# M2_Breakout.net
KiCad netlist of a schematic drawn in Altium Designer
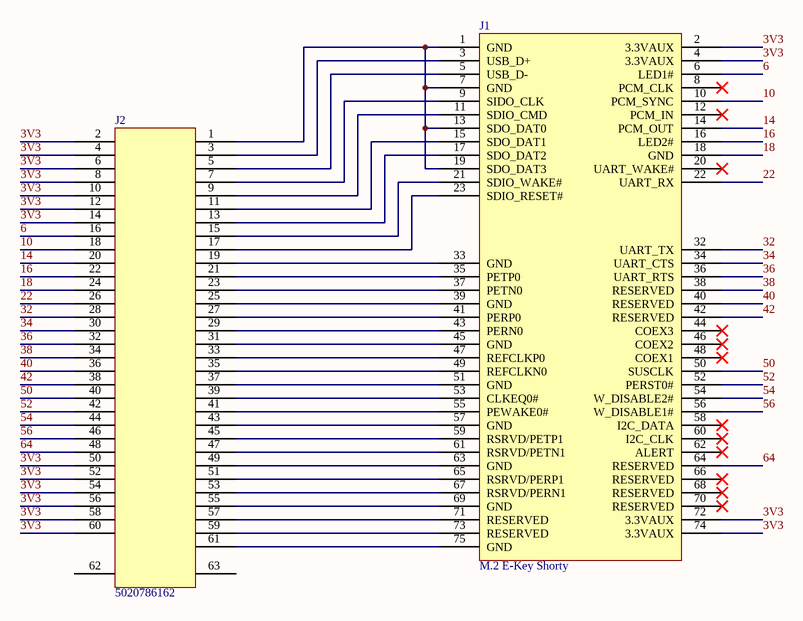
[diagram p0: M2 Breakout.SchDoc]

(export (version "E")
  (design (tool "Eeschema 10.0.6"))
  (components
    (comp (ref "J1")
      (value "M.2 E-Key Shorty")
      (footprint "M.2 E-Key Shorty")
      (libsource (lib "KBuchka-IntLib") (part "M.2 E-Key Shorty"))
    )
    (comp (ref "J2")
      (value "5020786162")
      (footprint "5020786162")
      (description "Conn FPC Connector SKT 61 POS 0.25mm Solder RA SMD T/R")
      (libsource (lib "KBuchka-IntLib") (part "5020786162"))
    )
  )
  (nets
    (net (code "1") (name "/3V3") (class "Default")
      (node (ref "J1") (pin "2") (pinfunction "3.3VAUX_2") (pintype "passive"))
      (node (ref "J1") (pin "4") (pinfunction "3.3VAUX_4") (pintype "passive"))
      (node (ref "J1") (pin "72") (pinfunction "3.3VAUX_72") (pintype "passive"))
      (node (ref "J1") (pin "74") (pinfunction "3.3VAUX_74") (pintype "passive"))
      (node (ref "J2") (pin "10") (pintype "passive"))
      (node (ref "J2") (pin "12") (pintype "passive"))
      (node (ref "J2") (pin "14") (pintype "passive"))
      (node (ref "J2") (pin "2") (pintype "passive"))
      (node (ref "J2") (pin "4") (pintype "passive"))
      (node (ref "J2") (pin "50") (pintype "passive"))
      (node (ref "J2") (pin "52") (pintype "passive"))
      (node (ref "J2") (pin "54") (pintype "passive"))
      (node (ref "J2") (pin "56") (pintype "passive"))
      (node (ref "J2") (pin "58") (pintype "passive"))
      (node (ref "J2") (pin "6") (pintype "passive"))
      (node (ref "J2") (pin "60") (pintype "passive"))
      (node (ref "J2") (pin "8") (pintype "passive"))
    )
    (net (code "2") (name "/6") (class "Default")
      (node (ref "J1") (pin "6") (pinfunction "LED1#_6") (pintype "passive"))
      (node (ref "J2") (pin "16") (pintype "passive"))
    )
    (net (code "3") (name "/10") (class "Default")
      (node (ref "J1") (pin "10") (pinfunction "PCM_SYNC_10") (pintype "passive"))
      (node (ref "J2") (pin "18") (pintype "passive"))
    )
    (net (code "4") (name "/14") (class "Default")
      (node (ref "J1") (pin "14") (pinfunction "PCM_OUT_14") (pintype "passive"))
      (node (ref "J2") (pin "20") (pintype "passive"))
    )
    (net (code "5") (name "/16") (class "Default")
      (node (ref "J1") (pin "16") (pinfunction "LED2#_16") (pintype "passive"))
      (node (ref "J2") (pin "22") (pintype "passive"))
    )
    (net (code "6") (name "/18") (class "Default")
      (node (ref "J1") (pin "18") (pinfunction "GND_18") (pintype "passive"))
      (node (ref "J2") (pin "24") (pintype "passive"))
    )
    (net (code "7") (name "/22") (class "Default")
      (node (ref "J1") (pin "22") (pinfunction "UART_RX_22") (pintype "passive"))
      (node (ref "J2") (pin "26") (pintype "passive"))
    )
    (net (code "8") (name "/32") (class "Default")
      (node (ref "J1") (pin "32") (pinfunction "UART_TX_32") (pintype "passive"))
      (node (ref "J2") (pin "28") (pintype "passive"))
    )
    (net (code "9") (name "/34") (class "Default")
      (node (ref "J1") (pin "34") (pinfunction "UART_CTS_34") (pintype "passive"))
      (node (ref "J2") (pin "30") (pintype "passive"))
    )
    (net (code "10") (name "/36") (class "Default")
      (node (ref "J1") (pin "36") (pinfunction "UART_RTS_36") (pintype "passive"))
      (node (ref "J2") (pin "32") (pintype "passive"))
    )
    (net (code "11") (name "/38") (class "Default")
      (node (ref "J1") (pin "38") (pinfunction "RESERVED_38") (pintype "passive"))
      (node (ref "J2") (pin "34") (pintype "passive"))
    )
    (net (code "12") (name "/40") (class "Default")
      (node (ref "J1") (pin "40") (pinfunction "RESERVED_40") (pintype "passive"))
      (node (ref "J2") (pin "36") (pintype "passive"))
    )
    (net (code "13") (name "/42") (class "Default")
      (node (ref "J1") (pin "42") (pinfunction "RESERVED_42") (pintype "passive"))
      (node (ref "J2") (pin "38") (pintype "passive"))
    )
    (net (code "14") (name "/50") (class "Default")
      (node (ref "J1") (pin "50") (pinfunction "SUSCLK_50") (pintype "passive"))
      (node (ref "J2") (pin "40") (pintype "passive"))
    )
    (net (code "15") (name "/52") (class "Default")
      (node (ref "J1") (pin "52") (pinfunction "PERST0#_52") (pintype "passive"))
      (node (ref "J2") (pin "42") (pintype "passive"))
    )
    (net (code "16") (name "/54") (class "Default")
      (node (ref "J1") (pin "54") (pinfunction "W_DISABLE2#_54") (pintype "passive"))
      (node (ref "J2") (pin "44") (pintype "passive"))
    )
    (net (code "17") (name "/56") (class "Default")
      (node (ref "J1") (pin "56") (pinfunction "W_DISABLE1#_56") (pintype "passive"))
      (node (ref "J2") (pin "46") (pintype "passive"))
    )
    (net (code "18") (name "/64") (class "Default")
      (node (ref "J1") (pin "64") (pinfunction "RESERVED_64") (pintype "passive"))
      (node (ref "J2") (pin "48") (pintype "passive"))
    )
    (net (code "19") (name "Net-(J1-CLKEQ0#)") (class "Default")
      (node (ref "J1") (pin "53") (pinfunction "CLKEQ0#_53") (pintype "passive"))
      (node (ref "J2") (pin "39") (pintype "passive"))
    )
    (net (code "20") (name "Net-(J1-GND-Pad33)") (class "Default")
      (node (ref "J1") (pin "33") (pinfunction "GND_33") (pintype "passive"))
      (node (ref "J2") (pin "19") (pintype "passive"))
    )
    (net (code "21") (name "Net-(J1-GND-Pad39)") (class "Default")
      (node (ref "J1") (pin "39") (pinfunction "GND_39") (pintype "passive"))
      (node (ref "J2") (pin "25") (pintype "passive"))
    )
    (net (code "22") (name "Net-(J1-GND-Pad45)") (class "Default")
      (node (ref "J1") (pin "45") (pinfunction "GND_45") (pintype "passive"))
      (node (ref "J2") (pin "31") (pintype "passive"))
    )
    (net (code "23") (name "Net-(J1-GND-Pad51)") (class "Default")
      (node (ref "J1") (pin "51") (pinfunction "GND_51") (pintype "passive"))
      (node (ref "J2") (pin "37") (pintype "passive"))
    )
    (net (code "24") (name "Net-(J1-GND-Pad57)") (class "Default")
      (node (ref "J1") (pin "57") (pinfunction "GND_57") (pintype "passive"))
      (node (ref "J2") (pin "43") (pintype "passive"))
    )
    (net (code "25") (name "Net-(J1-GND-Pad63)") (class "Default")
      (node (ref "J1") (pin "63") (pinfunction "GND_63") (pintype "passive"))
      (node (ref "J2") (pin "49") (pintype "passive"))
    )
    (net (code "26") (name "Net-(J1-GND-Pad69)") (class "Default")
      (node (ref "J1") (pin "69") (pinfunction "GND_69") (pintype "passive"))
      (node (ref "J2") (pin "55") (pintype "passive"))
    )
    (net (code "27") (name "Net-(J1-GND-Pad75)") (class "Default")
      (node (ref "J1") (pin "75") (pinfunction "GND_75") (pintype "passive"))
      (node (ref "J2") (pin "61") (pintype "passive"))
    )
    (net (code "28") (name "Net-(J1-PERN0)") (class "Default")
      (node (ref "J1") (pin "43") (pinfunction "PERN0_43") (pintype "passive"))
      (node (ref "J2") (pin "29") (pintype "passive"))
    )
    (net (code "29") (name "Net-(J1-PERP0)") (class "Default")
      (node (ref "J1") (pin "41") (pinfunction "PERP0_41") (pintype "passive"))
      (node (ref "J2") (pin "27") (pintype "passive"))
    )
    (net (code "30") (name "Net-(J1-PETN0)") (class "Default")
      (node (ref "J1") (pin "37") (pinfunction "PETN0_37") (pintype "passive"))
      (node (ref "J2") (pin "23") (pintype "passive"))
    )
    (net (code "31") (name "Net-(J1-PETP0)") (class "Default")
      (node (ref "J1") (pin "35") (pinfunction "PETP0_35") (pintype "passive"))
      (node (ref "J2") (pin "21") (pintype "passive"))
    )
    (net (code "32") (name "Net-(J1-PEWAKE0#)") (class "Default")
      (node (ref "J1") (pin "55") (pinfunction "PEWAKE0#_55") (pintype "passive"))
      (node (ref "J2") (pin "41") (pintype "passive"))
    )
    (net (code "33") (name "Net-(J1-REFCLKN0)") (class "Default")
      (node (ref "J1") (pin "49") (pinfunction "REFCLKN0_49") (pintype "passive"))
      (node (ref "J2") (pin "35") (pintype "passive"))
    )
    (net (code "34") (name "Net-(J1-REFCLKP0)") (class "Default")
      (node (ref "J1") (pin "47") (pinfunction "REFCLKP0_47") (pintype "passive"))
      (node (ref "J2") (pin "33") (pintype "passive"))
    )
    (net (code "35") (name "Net-(J1-RESERVED-Pad71)") (class "Default")
      (node (ref "J1") (pin "71") (pinfunction "RESERVED_71") (pintype "passive"))
      (node (ref "J2") (pin "57") (pintype "passive"))
    )
    (net (code "36") (name "Net-(J1-RESERVED-Pad73)") (class "Default")
      (node (ref "J1") (pin "73") (pinfunction "RESERVED_73") (pintype "passive"))
      (node (ref "J2") (pin "59") (pintype "passive"))
    )
    (net (code "37") (name "Net-(J1-RSRVD{slash}PERN1)") (class "Default")
      (node (ref "J1") (pin "67") (pinfunction "RSRVD/PERN1_67") (pintype "passive"))
      (node (ref "J2") (pin "53") (pintype "passive"))
    )
    (net (code "38") (name "Net-(J1-RSRVD{slash}PERP1)") (class "Default")
      (node (ref "J1") (pin "65") (pinfunction "RSRVD/PERP1_65") (pintype "passive"))
      (node (ref "J2") (pin "51") (pintype "passive"))
    )
    (net (code "39") (name "Net-(J1-RSRVD{slash}PETN1)") (class "Default")
      (node (ref "J1") (pin "61") (pinfunction "RSRVD/PETN1_61") (pintype "passive"))
      (node (ref "J2") (pin "47") (pintype "passive"))
    )
    (net (code "40") (name "Net-(J1-RSRVD{slash}PETP1)") (class "Default")
      (node (ref "J1") (pin "59") (pinfunction "RSRVD/PETP1_59") (pintype "passive"))
      (node (ref "J2") (pin "45") (pintype "passive"))
    )
    (net (code "41") (name "Net-(J1-SDIO_CMD)") (class "Default")
      (node (ref "J1") (pin "11") (pinfunction "SDIO_CMD_11") (pintype "passive"))
      (node (ref "J2") (pin "9") (pintype "passive"))
    )
    (net (code "42") (name "Net-(J1-SDIO_RESET#)") (class "Default")
      (node (ref "J1") (pin "23") (pinfunction "SDIO_RESET#_23") (pintype "passive"))
      (node (ref "J2") (pin "17") (pintype "passive"))
    )
    (net (code "43") (name "Net-(J1-SDIO_WAKE#)") (class "Default")
      (node (ref "J1") (pin "21") (pinfunction "SDIO_WAKE#_21") (pintype "passive"))
      (node (ref "J2") (pin "15") (pintype "passive"))
    )
    (net (code "44") (name "Net-(J1-SDO_DAT0)") (class "Default")
      (node (ref "J1") (pin "1") (pinfunction "GND_1") (pintype "passive"))
      (node (ref "J1") (pin "13") (pinfunction "SDO_DAT0_13") (pintype "passive"))
      (node (ref "J1") (pin "19") (pinfunction "SDO_DAT3_19") (pintype "passive"))
      (node (ref "J1") (pin "7") (pinfunction "GND_7") (pintype "passive"))
      (node (ref "J2") (pin "1") (pintype "passive"))
    )
    (net (code "45") (name "Net-(J1-SDO_DAT1)") (class "Default")
      (node (ref "J1") (pin "15") (pinfunction "SDO_DAT1_15") (pintype "passive"))
      (node (ref "J2") (pin "11") (pintype "passive"))
    )
    (net (code "46") (name "Net-(J1-SDO_DAT2)") (class "Default")
      (node (ref "J1") (pin "17") (pinfunction "SDO_DAT2_17") (pintype "passive"))
      (node (ref "J2") (pin "13") (pintype "passive"))
    )
    (net (code "47") (name "Net-(J1-SIDO_CLK)") (class "Default")
      (node (ref "J1") (pin "9") (pinfunction "SIDO_CLK_9") (pintype "passive"))
      (node (ref "J2") (pin "7") (pintype "passive"))
    )
    (net (code "48") (name "Net-(J1-USB_D+)") (class "Default")
      (node (ref "J1") (pin "3") (pinfunction "USB_D+_3") (pintype "passive"))
      (node (ref "J2") (pin "3") (pintype "passive"))
    )
    (net (code "49") (name "Net-(J1-USB_D-)") (class "Default")
      (node (ref "J1") (pin "5") (pinfunction "USB_D-_5") (pintype "passive"))
      (node (ref "J2") (pin "5") (pintype "passive"))
    )
    (net (code "50") (name "unconnected-(J1-ALERT-Pad62)") (class "Default")
      (node (ref "J1") (pin "62") (pinfunction "ALERT_62") (pintype "passive+no_connect"))
    )
    (net (code "51") (name "unconnected-(J1-COEX1-Pad48)") (class "Default")
      (node (ref "J1") (pin "48") (pinfunction "COEX1_48") (pintype "passive+no_connect"))
    )
    (net (code "52") (name "unconnected-(J1-COEX2-Pad46)") (class "Default")
      (node (ref "J1") (pin "46") (pinfunction "COEX2_46") (pintype "passive+no_connect"))
    )
    (net (code "53") (name "unconnected-(J1-COEX3-Pad44)") (class "Default")
      (node (ref "J1") (pin "44") (pinfunction "COEX3_44") (pintype "passive+no_connect"))
    )
    (net (code "54") (name "unconnected-(J1-I2C_CLK-Pad60)") (class "Default")
      (node (ref "J1") (pin "60") (pinfunction "I2C_CLK_60") (pintype "passive+no_connect"))
    )
    (net (code "55") (name "unconnected-(J1-I2C_DATA-Pad58)") (class "Default")
      (node (ref "J1") (pin "58") (pinfunction "I2C_DATA_58") (pintype "passive+no_connect"))
    )
    (net (code "56") (name "unconnected-(J1-PCM_CLK-Pad8)") (class "Default")
      (node (ref "J1") (pin "8") (pinfunction "PCM_CLK_8") (pintype "passive+no_connect"))
    )
    (net (code "57") (name "unconnected-(J1-PCM_IN-Pad12)") (class "Default")
      (node (ref "J1") (pin "12") (pinfunction "PCM_IN_12") (pintype "passive+no_connect"))
    )
    (net (code "58") (name "unconnected-(J1-RESERVED-Pad66)") (class "Default")
      (node (ref "J1") (pin "66") (pinfunction "RESERVED_66") (pintype "passive+no_connect"))
    )
    (net (code "59") (name "unconnected-(J1-RESERVED-Pad68)") (class "Default")
      (node (ref "J1") (pin "68") (pinfunction "RESERVED_68") (pintype "passive+no_connect"))
    )
    (net (code "60") (name "unconnected-(J1-RESERVED-Pad70)") (class "Default")
      (node (ref "J1") (pin "70") (pinfunction "RESERVED_70") (pintype "passive+no_connect"))
    )
    (net (code "61") (name "unconnected-(J1-UART_WAKE#-Pad20)") (class "Default")
      (node (ref "J1") (pin "20") (pinfunction "UART_WAKE#_20") (pintype "passive+no_connect"))
    )
    (net (code "62") (name "unconnected-(J2-Pad62)") (class "Default")
      (node (ref "J2") (pin "62") (pintype "passive"))
    )
    (net (code "63") (name "unconnected-(J2-Pad63)") (class "Default")
      (node (ref "J2") (pin "63") (pintype "passive"))
    )
  )
)
